# harp_to_ONIX_converter.net
KiCad netlist of a schematic drawn in EAGLE
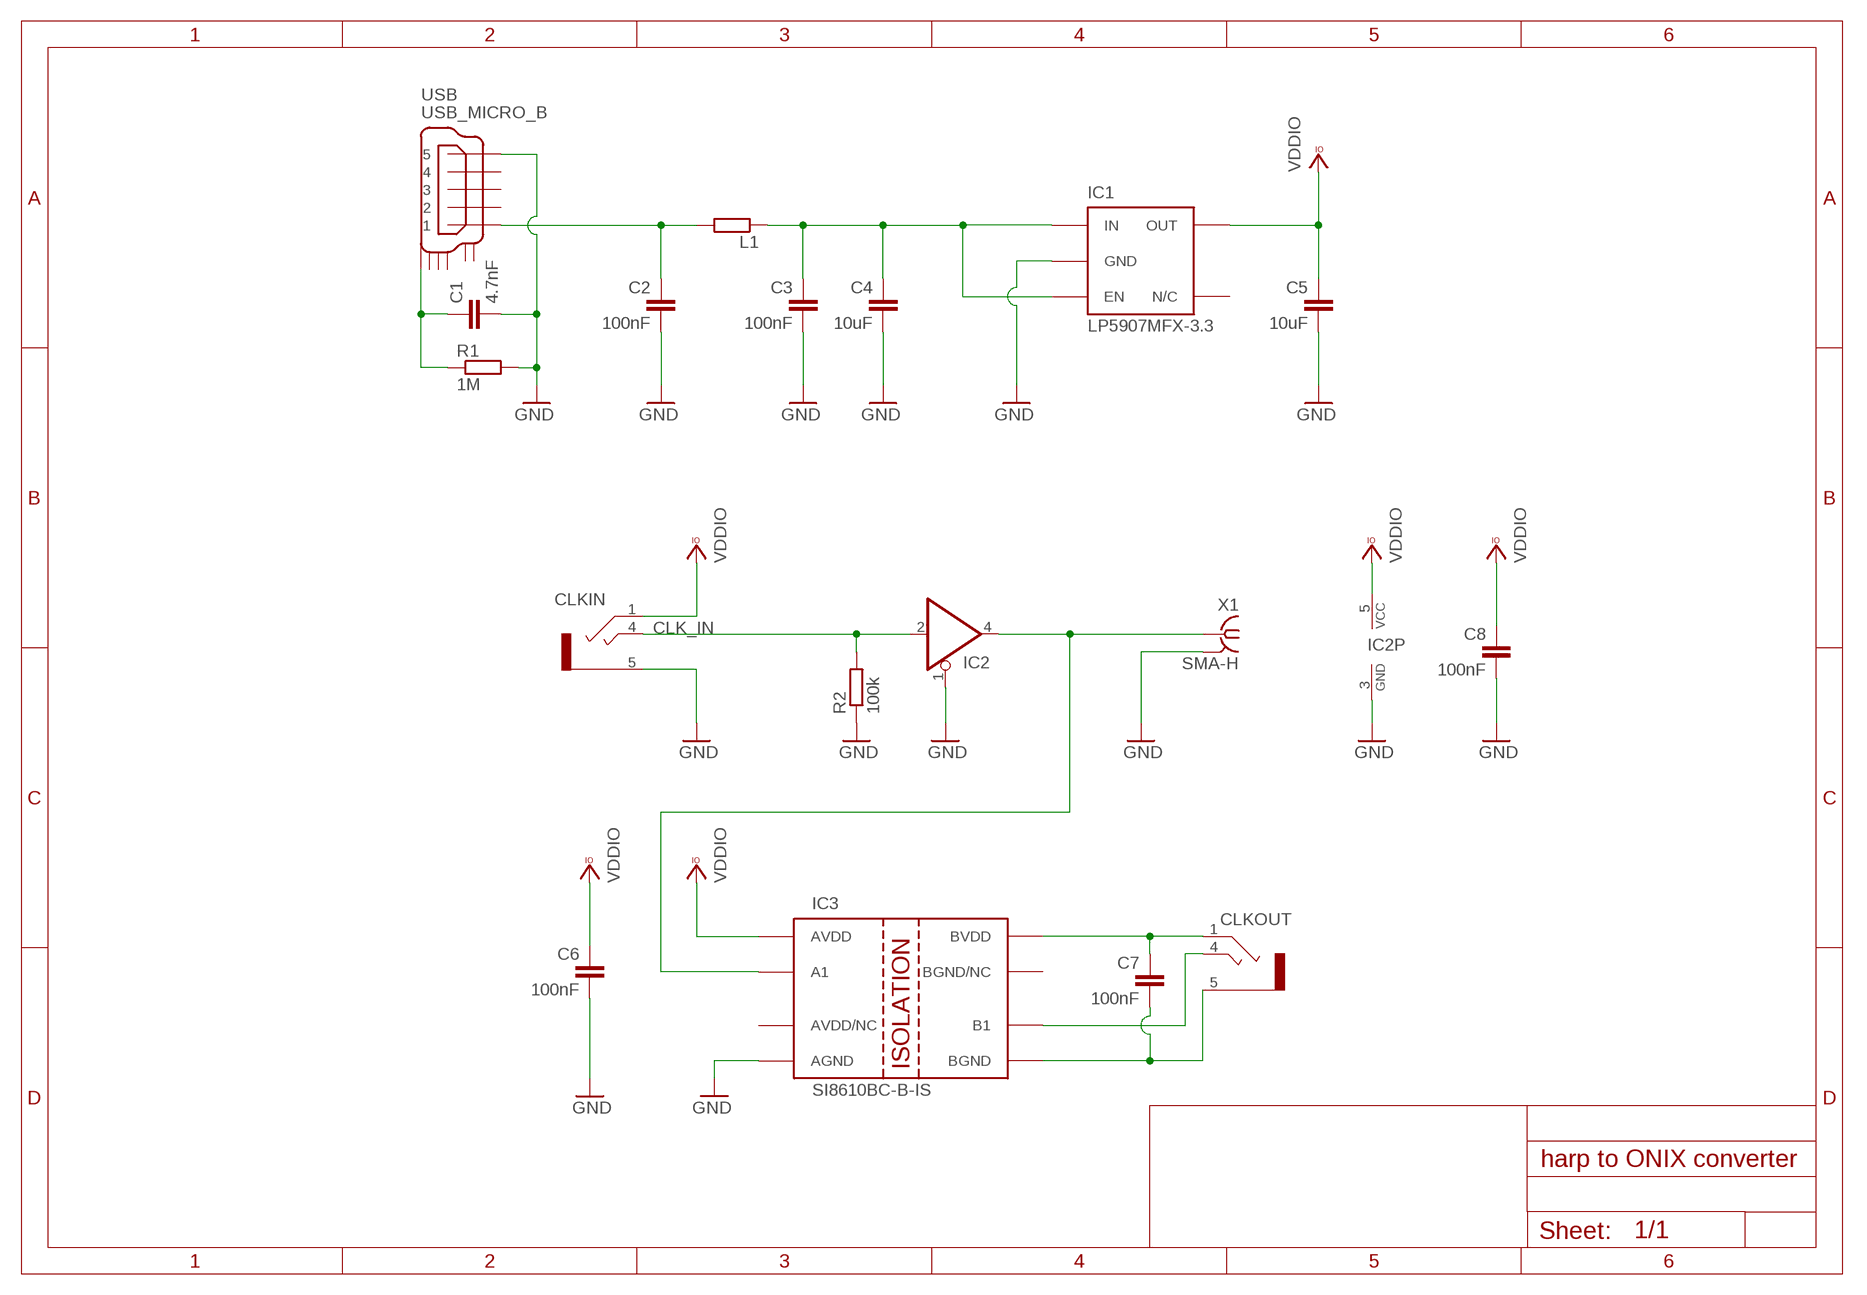
[diagram p0: schematic, sheet 1]

(export (version "E")
  (design (tool "Eeschema 10.0.6"))
  (components
    (comp (ref "C1")
      (value "4.7nF")
      (footprint "eagle-import:C0402")
      (libsource (lib "eagle-import") (part "C-EUC0402"))
    )
    (comp (ref "C2")
      (value "100nF")
      (footprint "eagle-import:C0402")
      (libsource (lib "eagle-import") (part "C-EUC0402"))
    )
    (comp (ref "C3")
      (value "100nF")
      (footprint "eagle-import:C0402")
      (libsource (lib "eagle-import") (part "C-EUC0402"))
    )
    (comp (ref "C4")
      (value "10uF")
      (footprint "eagle-import:C0603")
      (libsource (lib "eagle-import") (part "C-EUC0603"))
    )
    (comp (ref "C5")
      (value "10uF")
      (footprint "eagle-import:C0603")
      (libsource (lib "eagle-import") (part "C-EUC0603"))
    )
    (comp (ref "C6")
      (value "100nF")
      (footprint "eagle-import:C0402")
      (libsource (lib "eagle-import") (part "C-EUC0402"))
    )
    (comp (ref "C7")
      (value "100nF")
      (footprint "eagle-import:C0402")
      (fields (field (name "MPN") "MC0402B104K160CT"))
      (libsource (lib "eagle-import") (part "C-EUC0402"))
    )
    (comp (ref "C8")
      (value "100nF")
      (footprint "eagle-import:C0402")
      (libsource (lib "eagle-import") (part "C-EUC0402"))
    )
    (comp (ref "CLKIN")
      (value "STEREO_JACK")
      (footprint "eagle-import:35RASMT2BHNTRX")
      (libsource (lib "eagle-import") (part "STEREO_JACK"))
    )
    (comp (ref "CLKOUT")
      (value "CLCK_JACK")
      (footprint "eagle-import:35RASMT2BHNTRX")
      (fields (field (name "MPN") "35RASMT2BHNTRX"))
      (libsource (lib "eagle-import") (part "harp input expander_STEREO_JACK"))
    )
    (comp (ref "IC1")
      (value "LP5907MFX-3.3")
      (footprint "eagle-import:TSOT23-5")
      (libsource (lib "eagle-import") (part "TLV700XX"))
    )
    (comp (ref "IC2")
      (value "74AHC1G125DBV")
      (footprint "eagle-import:SOT23-5")
      (libsource (lib "eagle-import") (part "741G125DBVAHC"))
    )
    (comp (ref "IC3")
      (value "SI8610BC-B-IS")
      (footprint "eagle-import:SO-08")
      (fields (field (name "MPN") "SI8610EC-B-IS"))
      (libsource (lib "eagle-import") (part "SI8610"))
    )
    (comp (ref "L1")
      (value "???")
      (footprint "eagle-import:R0805")
      (libsource (lib "eagle-import") (part "R-EU_R0805"))
    )
    (comp (ref "R1")
      (value "1M")
      (footprint "eagle-import:R0402")
      (libsource (lib "eagle-import") (part "R-EU_R0402"))
    )
    (comp (ref "R2")
      (value "100k")
      (footprint "eagle-import:R0402")
      (libsource (lib "eagle-import") (part "R-EU_R0402"))
    )
    (comp (ref "USB")
      (value "USB_MICRO_B")
      (footprint "eagle-import:ZX62D-B-5P8")
      (libsource (lib "eagle-import") (part "USB_MICRO_B"))
    )
    (comp (ref "X1")
      (value "SMA-H")
      (footprint "eagle-import:BU-SMA-V")
      (libsource (lib "eagle-import") (part "BU-SMA-V"))
    )
  )
  (nets
    (net (code "1") (name "/CLK_IN") (class "Default")
      (node (ref "CLKIN") (pin "4") (pinfunction "4_4") (pintype "passive"))
      (node (ref "IC2") (pin "2") (pinfunction "I_2") (pintype "input"))
      (node (ref "R2") (pin "2") (pinfunction "2_2") (pintype "passive"))
    )
    (net (code "2") (name "GND") (class "Default")
      (node (ref "C1") (pin "2") (pinfunction "2_2") (pintype "passive"))
      (node (ref "C2") (pin "2") (pinfunction "2_2") (pintype "passive"))
      (node (ref "C3") (pin "2") (pinfunction "2_2") (pintype "passive"))
      (node (ref "C4") (pin "2") (pinfunction "2_2") (pintype "passive"))
      (node (ref "C5") (pin "2") (pinfunction "2_2") (pintype "passive"))
      (node (ref "C6") (pin "2") (pinfunction "2_2") (pintype "passive"))
      (node (ref "C8") (pin "2") (pinfunction "2_2") (pintype "passive"))
      (node (ref "CLKIN") (pin "5") (pinfunction "5_5") (pintype "passive"))
      (node (ref "IC1") (pin "2") (pinfunction "GND_2") (pintype "bidirectional"))
      (node (ref "IC2") (pin "1") (pinfunction "OE_1") (pintype "input"))
      (node (ref "IC2") (pin "3") (pinfunction "GND_3") (pintype "power_in"))
      (node (ref "IC3") (pin "4") (pinfunction "AGND_4") (pintype "bidirectional"))
      (node (ref "R1") (pin "2") (pinfunction "2_2") (pintype "passive"))
      (node (ref "R2") (pin "1") (pinfunction "1_1") (pintype "passive"))
      (node (ref "USB") (pin "P$5") (pinfunction "5_P$5") (pintype "bidirectional"))
      (node (ref "X1") (pin "2") (pinfunction "2_2") (pintype "passive"))
      (node (ref "X1") (pin "3") (pinfunction "2_3") (pintype "passive"))
      (node (ref "X1") (pin "4") (pinfunction "2_4") (pintype "passive"))
      (node (ref "X1") (pin "5") (pinfunction "2_5") (pintype "passive"))
    )
    (net (code "3") (name "Net-(IC1-EN)") (class "Default")
      (node (ref "C3") (pin "1") (pinfunction "1_1") (pintype "passive"))
      (node (ref "C4") (pin "1") (pinfunction "1_1") (pintype "passive"))
      (node (ref "IC1") (pin "1") (pinfunction "IN_1") (pintype "bidirectional"))
      (node (ref "IC1") (pin "3") (pinfunction "EN_3") (pintype "bidirectional"))
      (node (ref "L1") (pin "1") (pinfunction "1_1") (pintype "passive"))
    )
    (net (code "4") (name "Net-(IC2A-O)") (class "Default")
      (node (ref "IC2") (pin "4") (pinfunction "O_4") (pintype "tri_state"))
      (node (ref "IC3") (pin "2") (pinfunction "A1_2") (pintype "bidirectional"))
      (node (ref "X1") (pin "1") (pinfunction "1_1") (pintype "passive"))
    )
    (net (code "5") (name "Net-(IC3-B1)") (class "Default")
      (node (ref "CLKOUT") (pin "4") (pinfunction "4_4") (pintype "passive"))
      (node (ref "IC3") (pin "6") (pinfunction "B1_6") (pintype "bidirectional"))
    )
    (net (code "6") (name "Net-(IC3-BGND)") (class "Default")
      (node (ref "C7") (pin "2") (pinfunction "2_2") (pintype "passive"))
      (node (ref "CLKOUT") (pin "5") (pinfunction "5_5") (pintype "passive"))
      (node (ref "IC3") (pin "5") (pinfunction "BGND_5") (pintype "bidirectional"))
    )
    (net (code "7") (name "Net-(IC3-BVDD)") (class "Default")
      (node (ref "C7") (pin "1") (pinfunction "1_1") (pintype "passive"))
      (node (ref "CLKOUT") (pin "1") (pinfunction "1_1") (pintype "passive"))
      (node (ref "IC3") (pin "8") (pinfunction "BVDD_8") (pintype "bidirectional"))
    )
    (net (code "8") (name "Net-(USB-1)") (class "Default")
      (node (ref "C2") (pin "1") (pinfunction "1_1") (pintype "passive"))
      (node (ref "L1") (pin "2") (pinfunction "2_2") (pintype "passive"))
      (node (ref "USB") (pin "P$1") (pinfunction "1_P$1") (pintype "bidirectional"))
    )
    (net (code "9") (name "Net-(USB-P$4)") (class "Default")
      (node (ref "C1") (pin "1") (pinfunction "1_1") (pintype "passive"))
      (node (ref "R1") (pin "1") (pinfunction "1_1") (pintype "passive"))
      (node (ref "USB") (pin "SHIELD_4") (pinfunction "P$4_SHIELD_4") (pintype "bidirectional"))
    )
    (net (code "10") (name "VDDIO") (class "Default")
      (node (ref "C5") (pin "1") (pinfunction "1_1") (pintype "passive"))
      (node (ref "C6") (pin "1") (pinfunction "1_1") (pintype "passive"))
      (node (ref "C8") (pin "1") (pinfunction "1_1") (pintype "passive"))
      (node (ref "CLKIN") (pin "1") (pinfunction "1_1") (pintype "passive"))
      (node (ref "IC1") (pin "5") (pinfunction "OUT_5") (pintype "bidirectional"))
      (node (ref "IC2") (pin "5") (pinfunction "VCC_5") (pintype "power_in"))
      (node (ref "IC3") (pin "1") (pinfunction "AVDD_1") (pintype "bidirectional"))
    )
    (net (code "11") (name "unconnected-(IC1-N{slash}C-Pad4)") (class "Default")
      (node (ref "IC1") (pin "4") (pinfunction "N/C_4") (pintype "bidirectional"))
    )
    (net (code "12") (name "unconnected-(IC3-AVDD{slash}NC-Pad3)") (class "Default")
      (node (ref "IC3") (pin "3") (pinfunction "AVDD/NC_3") (pintype "bidirectional"))
    )
    (net (code "13") (name "unconnected-(IC3-BGND{slash}NC-Pad7)") (class "Default")
      (node (ref "IC3") (pin "7") (pinfunction "BGND/NC_7") (pintype "bidirectional"))
    )
    (net (code "14") (name "unconnected-(USB-2-PadP$2)") (class "Default")
      (node (ref "USB") (pin "P$2") (pinfunction "2_P$2") (pintype "bidirectional"))
    )
    (net (code "15") (name "unconnected-(USB-3-PadP$3)") (class "Default")
      (node (ref "USB") (pin "P$3") (pinfunction "3_P$3") (pintype "bidirectional"))
    )
    (net (code "16") (name "unconnected-(USB-4-PadP$4)") (class "Default")
      (node (ref "USB") (pin "P$4") (pinfunction "4_P$4") (pintype "bidirectional"))
    )
    (net (code "17") (name "unconnected-(USB-P$1-PadSHIELD_3)") (class "Default")
      (node (ref "USB") (pin "SHIELD_3") (pinfunction "P$1_SHIELD_3") (pintype "bidirectional"))
    )
    (net (code "18") (name "unconnected-(USB-P$2-PadSHIELD_1)") (class "Default")
      (node (ref "USB") (pin "SHIELD_1") (pinfunction "P$2_SHIELD_1") (pintype "bidirectional"))
    )
    (net (code "19") (name "unconnected-(USB-P$3-PadSHIELD_2)") (class "Default")
      (node (ref "USB") (pin "SHIELD_2") (pinfunction "P$3_SHIELD_2") (pintype "bidirectional"))
    )
    (net (code "20") (name "unconnected-(USB-P$5-PadP$6)") (class "Default")
      (node (ref "USB") (pin "P$6") (pinfunction "P$5_P$6") (pintype "bidirectional"))
    )
    (net (code "21") (name "unconnected-(USB-P$6-PadP$7)") (class "Default")
      (node (ref "USB") (pin "P$7") (pinfunction "P$6_P$7") (pintype "bidirectional"))
    )
  )
)
